# QuadCopter.net
KiCad netlist of a schematic drawn in EAGLE
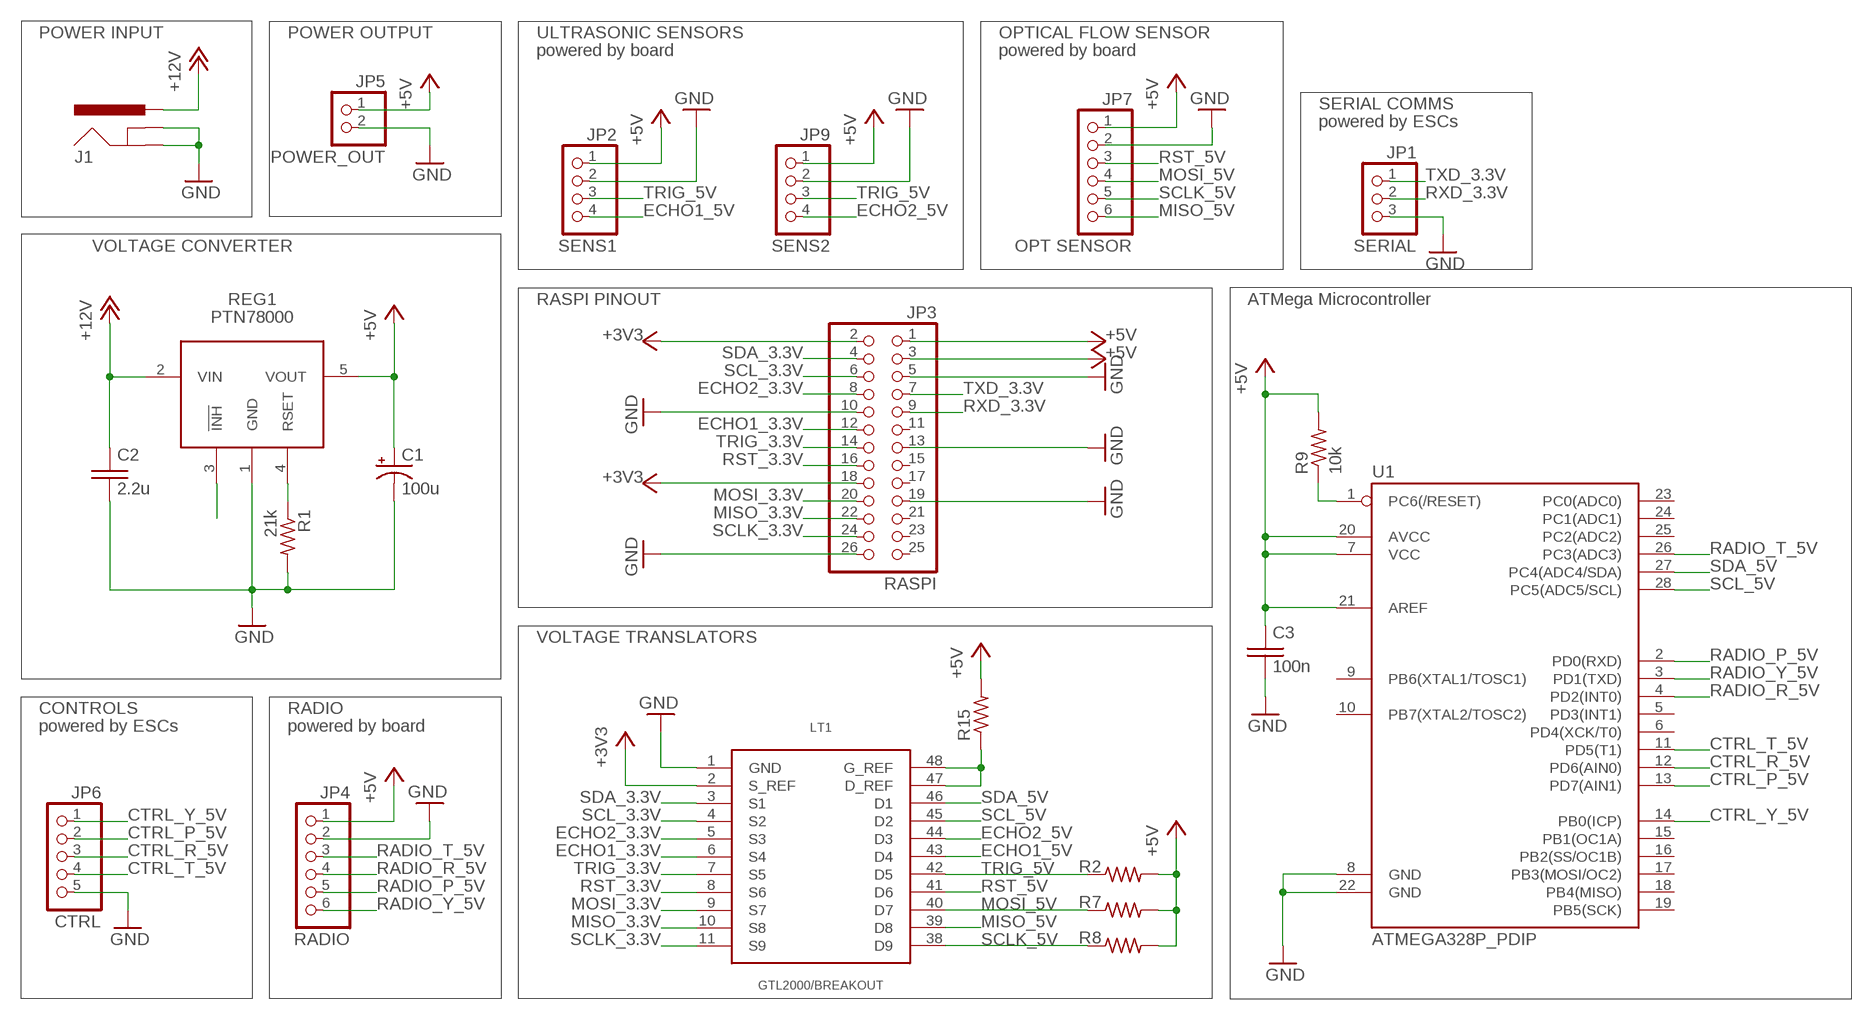
[diagram p0: schematic, sheet 1]

(export (version "E")
  (design (tool "Eeschema 10.0.6"))
  (components
    (comp (ref "C1")
      (value "100u")
      (footprint "eagle-import:153CLV-0605")
      (libsource (lib "eagle-import") (part "CPOL-US153CLV-0605"))
    )
    (comp (ref "C2")
      (value "2.2u")
      (footprint "eagle-import:C050-025X075")
      (libsource (lib "eagle-import") (part "C-US050-025X075"))
    )
    (comp (ref "C3")
      (value "100n")
      (footprint "eagle-import:C050-025X075")
      (libsource (lib "eagle-import") (part "C-US050-025X075"))
    )
    (comp (ref "J1")
      (value "POWER_JACKSLT")
      (footprint "eagle-import:POWER_JACK_SLOT")
      (libsource (lib "eagle-import") (part "POWER_JACKSLT"))
    )
    (comp (ref "JP1")
      (value "SERIAL")
      (footprint "eagle-import:1X03")
      (libsource (lib "eagle-import") (part "PINHD-1X3"))
    )
    (comp (ref "JP2")
      (value "SENS1")
      (footprint "eagle-import:1X04")
      (libsource (lib "eagle-import") (part "PINHD-1X4"))
    )
    (comp (ref "JP3")
      (value "RASPI")
      (footprint "eagle-import:2X13_SMD")
      (libsource (lib "eagle-import") (part "PINHD-2X13/SMD"))
    )
    (comp (ref "JP4")
      (value "RADIO")
      (footprint "eagle-import:1X06")
      (libsource (lib "eagle-import") (part "PINHD-1X6"))
    )
    (comp (ref "JP5")
      (value "POWER_OUT")
      (footprint "eagle-import:1X02")
      (libsource (lib "eagle-import") (part "PINHD-1X2"))
    )
    (comp (ref "JP6")
      (value "CTRL")
      (footprint "eagle-import:1X05")
      (libsource (lib "eagle-import") (part "PINHD-1X5"))
    )
    (comp (ref "JP7")
      (value "OPT SENSOR")
      (footprint "eagle-import:1X06")
      (libsource (lib "eagle-import") (part "PINHD-1X6"))
    )
    (comp (ref "JP9")
      (value "SENS2")
      (footprint "eagle-import:1X04")
      (libsource (lib "eagle-import") (part "PINHD-1X4"))
    )
    (comp (ref "LT1")
      (value "GTL2000/BREAKOUT")
      (footprint "eagle-import:TSSOP48_BREAKOUT")
      (libsource (lib "eagle-import") (part "GTL2000/BREAKOUT"))
    )
    (comp (ref "R1")
      (value "21k")
      (footprint "eagle-import:0207_10")
      (libsource (lib "eagle-import") (part "R-US_0207/10"))
    )
    (comp (ref "R2")
      (value "R-US_0207/12")
      (footprint "eagle-import:0207_12")
      (libsource (lib "eagle-import") (part "R-US_0207/12"))
    )
    (comp (ref "R7")
      (value "R-US_0207/12")
      (footprint "eagle-import:0207_12")
      (libsource (lib "eagle-import") (part "R-US_0207/12"))
    )
    (comp (ref "R8")
      (value "R-US_0207/12")
      (footprint "eagle-import:0207_12")
      (libsource (lib "eagle-import") (part "R-US_0207/12"))
    )
    (comp (ref "R9")
      (value "10k")
      (footprint "eagle-import:0207_10")
      (libsource (lib "eagle-import") (part "R-US_0207/10"))
    )
    (comp (ref "R15")
      (value "R-US_0207/10")
      (footprint "eagle-import:0207_10")
      (libsource (lib "eagle-import") (part "R-US_0207/10"))
    )
    (comp (ref "REG1")
      (value "PTN78000")
      (footprint "eagle-import:PTN78000")
      (libsource (lib "eagle-import") (part "PTN78000"))
    )
    (comp (ref "U1")
      (value "ATMEGA328P_PDIP")
      (footprint "eagle-import:DIL28-3")
      (libsource (lib "eagle-import") (part "ATMEGA328P_PDIP"))
    )
  )
  (nets
    (net (code "1") (name "+3V3") (class "Default")
      (node (ref "JP3") (pin "18") (pinfunction "18_18") (pintype "passive"))
      (node (ref "JP3") (pin "2") (pinfunction "2_2") (pintype "passive"))
      (node (ref "LT1") (pin "2") (pinfunction "S_REF_2") (pintype "bidirectional"))
    )
    (net (code "2") (name "+5V") (class "Default")
      (node (ref "C1") (pin "+") (pinfunction "+_+") (pintype "passive"))
      (node (ref "C3") (pin "1") (pinfunction "1_1") (pintype "passive"))
      (node (ref "JP2") (pin "1") (pinfunction "1_1") (pintype "passive"))
      (node (ref "JP3") (pin "1") (pinfunction "1_1") (pintype "passive"))
      (node (ref "JP3") (pin "3") (pinfunction "3_3") (pintype "passive"))
      (node (ref "JP4") (pin "1") (pinfunction "1_1") (pintype "passive"))
      (node (ref "JP5") (pin "1") (pinfunction "1_1") (pintype "passive"))
      (node (ref "JP7") (pin "1") (pinfunction "1_1") (pintype "passive"))
      (node (ref "JP9") (pin "1") (pinfunction "1_1") (pintype "passive"))
      (node (ref "R15") (pin "2") (pinfunction "2_2") (pintype "passive"))
      (node (ref "R2") (pin "2") (pinfunction "2_2") (pintype "passive"))
      (node (ref "R7") (pin "2") (pinfunction "2_2") (pintype "passive"))
      (node (ref "R8") (pin "2") (pinfunction "2_2") (pintype "passive"))
      (node (ref "R9") (pin "2") (pinfunction "2_2") (pintype "passive"))
      (node (ref "REG1") (pin "5") (pinfunction "VOUT_5") (pintype "bidirectional"))
      (node (ref "U1") (pin "20") (pinfunction "AVCC_20") (pintype "bidirectional"))
      (node (ref "U1") (pin "21") (pinfunction "AREF_21") (pintype "bidirectional"))
      (node (ref "U1") (pin "7") (pinfunction "VCC_7") (pintype "bidirectional"))
    )
    (net (code "3") (name "+12V") (class "Default")
      (node (ref "C2") (pin "1") (pinfunction "1_1") (pintype "passive"))
      (node (ref "J1") (pin "PWR") (pinfunction "PWR_PWR") (pintype "bidirectional"))
      (node (ref "REG1") (pin "2") (pinfunction "VIN_2") (pintype "bidirectional"))
    )
    (net (code "4") (name "/CTRL_P_5V") (class "Default")
      (node (ref "JP6") (pin "2") (pinfunction "2_2") (pintype "passive"))
      (node (ref "U1") (pin "13") (pinfunction "PD7(AIN1)_13") (pintype "bidirectional"))
    )
    (net (code "5") (name "/CTRL_R_5V") (class "Default")
      (node (ref "JP6") (pin "3") (pinfunction "3_3") (pintype "passive"))
      (node (ref "U1") (pin "12") (pinfunction "PD6(AIN0)_12") (pintype "bidirectional"))
    )
    (net (code "6") (name "/CTRL_T_5V") (class "Default")
      (node (ref "JP6") (pin "4") (pinfunction "4_4") (pintype "passive"))
      (node (ref "U1") (pin "11") (pinfunction "PD5(T1)_11") (pintype "bidirectional"))
    )
    (net (code "7") (name "/CTRL_Y_5V") (class "Default")
      (node (ref "JP6") (pin "1") (pinfunction "1_1") (pintype "passive"))
      (node (ref "U1") (pin "14") (pinfunction "PB0(ICP)_14") (pintype "bidirectional"))
    )
    (net (code "8") (name "/ECHO1_3.3V") (class "Default")
      (node (ref "JP3") (pin "12") (pinfunction "12_12") (pintype "passive"))
      (node (ref "LT1") (pin "6") (pinfunction "S4_6") (pintype "bidirectional"))
    )
    (net (code "9") (name "/ECHO1_5V") (class "Default")
      (node (ref "JP2") (pin "4") (pinfunction "4_4") (pintype "passive"))
      (node (ref "LT1") (pin "43") (pinfunction "D4_43") (pintype "bidirectional"))
    )
    (net (code "10") (name "/ECHO2_3.3V") (class "Default")
      (node (ref "JP3") (pin "8") (pinfunction "8_8") (pintype "passive"))
      (node (ref "LT1") (pin "5") (pinfunction "S3_5") (pintype "bidirectional"))
    )
    (net (code "11") (name "/ECHO2_5V") (class "Default")
      (node (ref "JP9") (pin "4") (pinfunction "4_4") (pintype "passive"))
      (node (ref "LT1") (pin "44") (pinfunction "D3_44") (pintype "bidirectional"))
    )
    (net (code "12") (name "/MISO_3.3V") (class "Default")
      (node (ref "JP3") (pin "22") (pinfunction "22_22") (pintype "passive"))
      (node (ref "LT1") (pin "10") (pinfunction "S8_10") (pintype "bidirectional"))
    )
    (net (code "13") (name "/MISO_5V") (class "Default")
      (node (ref "JP7") (pin "6") (pinfunction "6_6") (pintype "passive"))
      (node (ref "LT1") (pin "39") (pinfunction "D8_39") (pintype "bidirectional"))
    )
    (net (code "14") (name "/MOSI_3.3V") (class "Default")
      (node (ref "JP3") (pin "20") (pinfunction "20_20") (pintype "passive"))
      (node (ref "LT1") (pin "9") (pinfunction "S7_9") (pintype "bidirectional"))
    )
    (net (code "15") (name "/MOSI_5V") (class "Default")
      (node (ref "JP7") (pin "4") (pinfunction "4_4") (pintype "passive"))
      (node (ref "LT1") (pin "40") (pinfunction "D7_40") (pintype "bidirectional"))
      (node (ref "R7") (pin "1") (pinfunction "1_1") (pintype "passive"))
    )
    (net (code "16") (name "/RADIO_P_5V") (class "Default")
      (node (ref "JP4") (pin "5") (pinfunction "5_5") (pintype "passive"))
      (node (ref "U1") (pin "2") (pinfunction "PD0(RXD)_2") (pintype "bidirectional"))
    )
    (net (code "17") (name "/RADIO_R_5V") (class "Default")
      (node (ref "JP4") (pin "4") (pinfunction "4_4") (pintype "passive"))
      (node (ref "U1") (pin "4") (pinfunction "PD2(INT0)_4") (pintype "bidirectional"))
    )
    (net (code "18") (name "/RADIO_T_5V") (class "Default")
      (node (ref "JP4") (pin "3") (pinfunction "3_3") (pintype "passive"))
      (node (ref "U1") (pin "26") (pinfunction "PC3(ADC3)_26") (pintype "bidirectional"))
    )
    (net (code "19") (name "/RADIO_Y_5V") (class "Default")
      (node (ref "JP4") (pin "6") (pinfunction "6_6") (pintype "passive"))
      (node (ref "U1") (pin "3") (pinfunction "PD1(TXD)_3") (pintype "bidirectional"))
    )
    (net (code "20") (name "/RST_3.3V") (class "Default")
      (node (ref "JP3") (pin "16") (pinfunction "16_16") (pintype "passive"))
      (node (ref "LT1") (pin "8") (pinfunction "S6_8") (pintype "bidirectional"))
    )
    (net (code "21") (name "/RST_5V") (class "Default")
      (node (ref "JP7") (pin "3") (pinfunction "3_3") (pintype "passive"))
      (node (ref "LT1") (pin "41") (pinfunction "D6_41") (pintype "bidirectional"))
    )
    (net (code "22") (name "/RXD_3.3V") (class "Default")
      (node (ref "JP1") (pin "2") (pinfunction "2_2") (pintype "passive"))
      (node (ref "JP3") (pin "9") (pinfunction "9_9") (pintype "passive"))
    )
    (net (code "23") (name "/SCLK_3.3V") (class "Default")
      (node (ref "JP3") (pin "24") (pinfunction "24_24") (pintype "passive"))
      (node (ref "LT1") (pin "11") (pinfunction "S9_11") (pintype "bidirectional"))
    )
    (net (code "24") (name "/SCLK_5V") (class "Default")
      (node (ref "JP7") (pin "5") (pinfunction "5_5") (pintype "passive"))
      (node (ref "LT1") (pin "38") (pinfunction "D9_38") (pintype "bidirectional"))
      (node (ref "R8") (pin "1") (pinfunction "1_1") (pintype "passive"))
    )
    (net (code "25") (name "/SCL_3.3V") (class "Default")
      (node (ref "JP3") (pin "6") (pinfunction "6_6") (pintype "passive"))
      (node (ref "LT1") (pin "4") (pinfunction "S2_4") (pintype "bidirectional"))
    )
    (net (code "26") (name "/SCL_5V") (class "Default")
      (node (ref "LT1") (pin "45") (pinfunction "D2_45") (pintype "bidirectional"))
      (node (ref "U1") (pin "28") (pinfunction "PC5(ADC5/SCL)_28") (pintype "bidirectional"))
    )
    (net (code "27") (name "/SDA_3.3V") (class "Default")
      (node (ref "JP3") (pin "4") (pinfunction "4_4") (pintype "passive"))
      (node (ref "LT1") (pin "3") (pinfunction "S1_3") (pintype "bidirectional"))
    )
    (net (code "28") (name "/SDA_5V") (class "Default")
      (node (ref "LT1") (pin "46") (pinfunction "D1_46") (pintype "bidirectional"))
      (node (ref "U1") (pin "27") (pinfunction "PC4(ADC4/SDA)_27") (pintype "bidirectional"))
    )
    (net (code "29") (name "/TRIG_3.3V") (class "Default")
      (node (ref "JP3") (pin "14") (pinfunction "14_14") (pintype "passive"))
      (node (ref "LT1") (pin "7") (pinfunction "S5_7") (pintype "bidirectional"))
    )
    (net (code "30") (name "/TRIG_5V") (class "Default")
      (node (ref "JP2") (pin "3") (pinfunction "3_3") (pintype "passive"))
      (node (ref "JP9") (pin "3") (pinfunction "3_3") (pintype "passive"))
      (node (ref "LT1") (pin "42") (pinfunction "D5_42") (pintype "bidirectional"))
      (node (ref "R2") (pin "1") (pinfunction "1_1") (pintype "passive"))
    )
    (net (code "31") (name "/TXD_3.3V") (class "Default")
      (node (ref "JP1") (pin "1") (pinfunction "1_1") (pintype "passive"))
      (node (ref "JP3") (pin "7") (pinfunction "7_7") (pintype "passive"))
    )
    (net (code "32") (name "GND") (class "Default")
      (node (ref "C1") (pin "-") (pinfunction "-_-") (pintype "passive"))
      (node (ref "C2") (pin "2") (pinfunction "2_2") (pintype "passive"))
      (node (ref "C3") (pin "2") (pinfunction "2_2") (pintype "passive"))
      (node (ref "J1") (pin "GND@1") (pinfunction "GNDBREAK_GND@1") (pintype "bidirectional"))
      (node (ref "J1") (pin "GND@2") (pinfunction "GND_GND@2") (pintype "bidirectional"))
      (node (ref "JP1") (pin "3") (pinfunction "3_3") (pintype "passive"))
      (node (ref "JP2") (pin "2") (pinfunction "2_2") (pintype "passive"))
      (node (ref "JP3") (pin "10") (pinfunction "10_10") (pintype "passive"))
      (node (ref "JP3") (pin "13") (pinfunction "13_13") (pintype "passive"))
      (node (ref "JP3") (pin "19") (pinfunction "19_19") (pintype "passive"))
      (node (ref "JP3") (pin "26") (pinfunction "26_26") (pintype "passive"))
      (node (ref "JP3") (pin "5") (pinfunction "5_5") (pintype "passive"))
      (node (ref "JP4") (pin "2") (pinfunction "2_2") (pintype "passive"))
      (node (ref "JP5") (pin "2") (pinfunction "2_2") (pintype "passive"))
      (node (ref "JP6") (pin "5") (pinfunction "5_5") (pintype "passive"))
      (node (ref "JP7") (pin "2") (pinfunction "2_2") (pintype "passive"))
      (node (ref "JP9") (pin "2") (pinfunction "2_2") (pintype "passive"))
      (node (ref "LT1") (pin "1") (pinfunction "GND_1") (pintype "bidirectional"))
      (node (ref "R1") (pin "2") (pinfunction "2_2") (pintype "passive"))
      (node (ref "REG1") (pin "1") (pinfunction "GND_1") (pintype "bidirectional"))
      (node (ref "U1") (pin "22") (pinfunction "GND_22") (pintype "bidirectional"))
      (node (ref "U1") (pin "8") (pinfunction "GND_8") (pintype "bidirectional"))
    )
    (net (code "33") (name "Net-(LT1-D_REF)") (class "Default")
      (node (ref "LT1") (pin "47") (pinfunction "D_REF_47") (pintype "bidirectional"))
      (node (ref "LT1") (pin "48") (pinfunction "G_REF_48") (pintype "bidirectional"))
      (node (ref "R15") (pin "1") (pinfunction "1_1") (pintype "passive"))
    )
    (net (code "34") (name "Net-(REG1-RSET)") (class "Default")
      (node (ref "R1") (pin "1") (pinfunction "1_1") (pintype "passive"))
      (node (ref "REG1") (pin "4") (pinfunction "RSET_4") (pintype "bidirectional"))
    )
    (net (code "35") (name "Net-(U1-PC6({slash}RESET))") (class "Default")
      (node (ref "R9") (pin "1") (pinfunction "1_1") (pintype "passive"))
      (node (ref "U1") (pin "1") (pinfunction "PC6(/RESET)_1") (pintype "bidirectional"))
    )
    (net (code "36") (name "unconnected-(JP3-Pad11)") (class "Default")
      (node (ref "JP3") (pin "11") (pinfunction "11_11") (pintype "passive"))
    )
    (net (code "37") (name "unconnected-(JP3-Pad15)") (class "Default")
      (node (ref "JP3") (pin "15") (pinfunction "15_15") (pintype "passive"))
    )
    (net (code "38") (name "unconnected-(JP3-Pad17)") (class "Default")
      (node (ref "JP3") (pin "17") (pinfunction "17_17") (pintype "passive"))
    )
    (net (code "39") (name "unconnected-(JP3-Pad21)") (class "Default")
      (node (ref "JP3") (pin "21") (pinfunction "21_21") (pintype "passive"))
    )
    (net (code "40") (name "unconnected-(JP3-Pad23)") (class "Default")
      (node (ref "JP3") (pin "23") (pinfunction "23_23") (pintype "passive"))
    )
    (net (code "41") (name "unconnected-(JP3-Pad25)") (class "Default")
      (node (ref "JP3") (pin "25") (pinfunction "25_25") (pintype "passive"))
    )
    (net (code "42") (name "unconnected-(REG1-~{INH}-Pad3)") (class "Default")
      (node (ref "REG1") (pin "3") (pinfunction "~{INH}_3") (pintype "bidirectional"))
    )
    (net (code "43") (name "unconnected-(U1-PB1(OC1A)-Pad15)") (class "Default")
      (node (ref "U1") (pin "15") (pinfunction "PB1(OC1A)_15") (pintype "bidirectional"))
    )
    (net (code "44") (name "unconnected-(U1-PB2(SS{slash}OC1B)-Pad16)") (class "Default")
      (node (ref "U1") (pin "16") (pinfunction "PB2(SS/OC1B)_16") (pintype "bidirectional"))
    )
    (net (code "45") (name "unconnected-(U1-PB3(MOSI{slash}OC2)-Pad17)") (class "Default")
      (node (ref "U1") (pin "17") (pinfunction "PB3(MOSI/OC2)_17") (pintype "bidirectional"))
    )
    (net (code "46") (name "unconnected-(U1-PB4(MISO)-Pad18)") (class "Default")
      (node (ref "U1") (pin "18") (pinfunction "PB4(MISO)_18") (pintype "bidirectional"))
    )
    (net (code "47") (name "unconnected-(U1-PB5(SCK)-Pad19)") (class "Default")
      (node (ref "U1") (pin "19") (pinfunction "PB5(SCK)_19") (pintype "bidirectional"))
    )
    (net (code "48") (name "unconnected-(U1-PB6(XTAL1{slash}TOSC1)-Pad9)") (class "Default")
      (node (ref "U1") (pin "9") (pinfunction "PB6(XTAL1/TOSC1)_9") (pintype "bidirectional"))
    )
    (net (code "49") (name "unconnected-(U1-PB7(XTAL2{slash}TOSC2)-Pad10)") (class "Default")
      (node (ref "U1") (pin "10") (pinfunction "PB7(XTAL2/TOSC2)_10") (pintype "bidirectional"))
    )
    (net (code "50") (name "unconnected-(U1-PC0(ADC0)-Pad23)") (class "Default")
      (node (ref "U1") (pin "23") (pinfunction "PC0(ADC0)_23") (pintype "bidirectional"))
    )
    (net (code "51") (name "unconnected-(U1-PC1(ADC1)-Pad24)") (class "Default")
      (node (ref "U1") (pin "24") (pinfunction "PC1(ADC1)_24") (pintype "bidirectional"))
    )
    (net (code "52") (name "unconnected-(U1-PC2(ADC2)-Pad25)") (class "Default")
      (node (ref "U1") (pin "25") (pinfunction "PC2(ADC2)_25") (pintype "bidirectional"))
    )
    (net (code "53") (name "unconnected-(U1-PD3(INT1)-Pad5)") (class "Default")
      (node (ref "U1") (pin "5") (pinfunction "PD3(INT1)_5") (pintype "bidirectional"))
    )
    (net (code "54") (name "unconnected-(U1-PD4(XCK{slash}T0)-Pad6)") (class "Default")
      (node (ref "U1") (pin "6") (pinfunction "PD4(XCK/T0)_6") (pintype "bidirectional"))
    )
  )
)
